# Step_counter.net
KiCad netlist of a schematic drawn in EAGLE
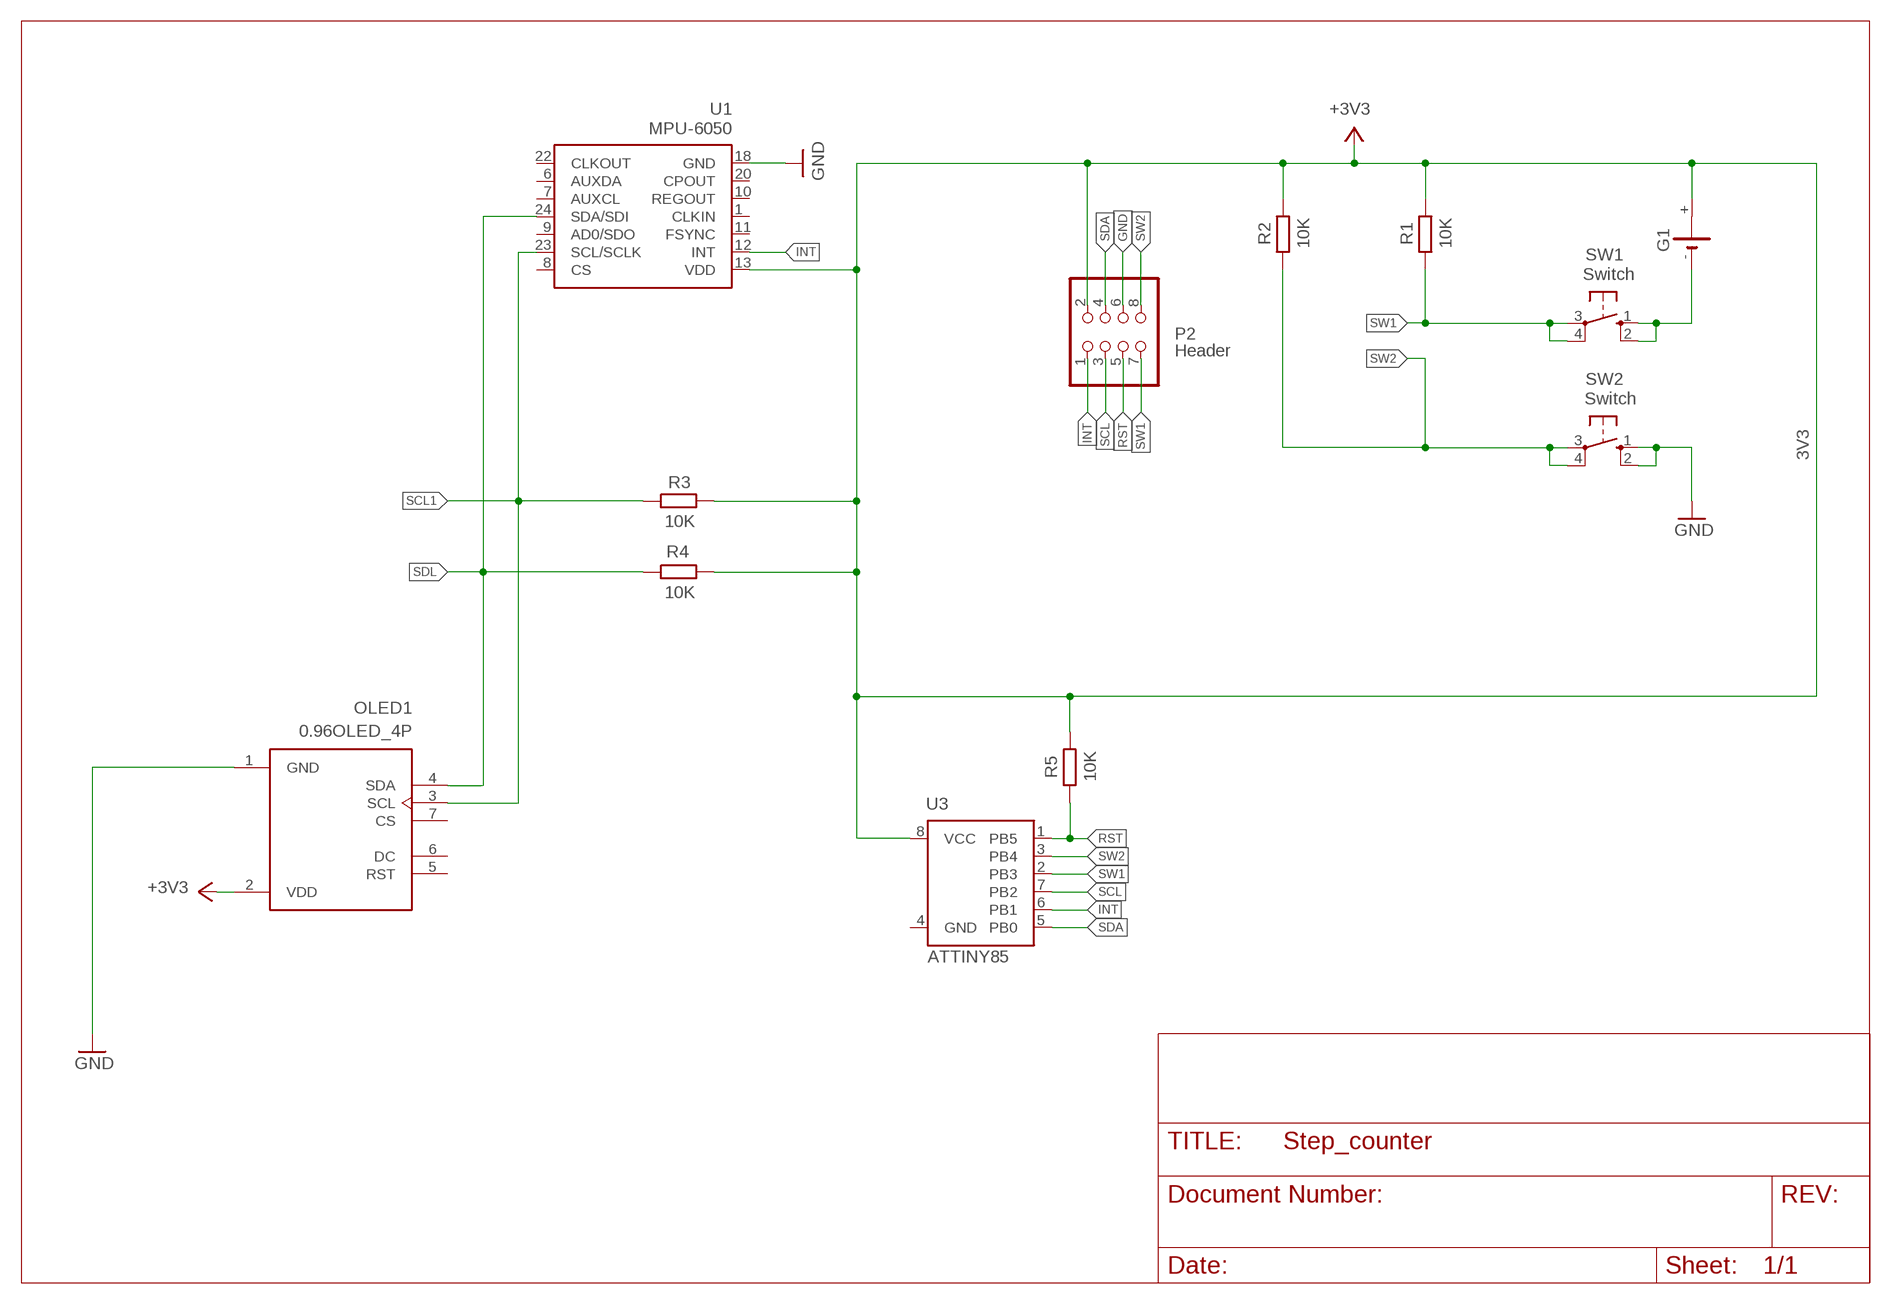
[diagram p0: schematic, sheet 1]

(export (version "E")
  (design (tool "Eeschema 10.0.6"))
  (components
    (comp (ref "G1")
      (value "3V3")
      (footprint "eagle-import:CR2032V")
      (libsource (lib "eagle-import") (part "CR2032V"))
    )
    (comp (ref "OLED1")
      (value "0.96OLED_4P")
      (footprint "eagle-import:LCD_AOM12864A0-1.54WW-ANO")
      (fields (field (name "MF") "Orient Display") (field (name "MP") "AOM12864A0-1.54WW-ANO"))
      (libsource (lib "eagle-import") (part "AOM12864A0-1.54WW-ANO"))
    )
    (comp (ref "P2")
      (value "Header")
      (footprint "eagle-import:2X04")
      (libsource (lib "eagle-import") (part "PINHD-2X4"))
    )
    (comp (ref "R1")
      (value "10K")
      (footprint "eagle-import:0204_7")
      (libsource (lib "eagle-import") (part "R-EU_0204/7"))
    )
    (comp (ref "R2")
      (value "10K")
      (footprint "eagle-import:0204_7")
      (libsource (lib "eagle-import") (part "R-EU_0204/7"))
    )
    (comp (ref "R3")
      (value "10K")
      (footprint "eagle-import:0204_7")
      (libsource (lib "eagle-import") (part "R-EU_0204/7"))
    )
    (comp (ref "R4")
      (value "10K")
      (footprint "eagle-import:0204_7")
      (libsource (lib "eagle-import") (part "R-EU_0204/7"))
    )
    (comp (ref "R5")
      (value "10K")
      (footprint "eagle-import:0204_7")
      (libsource (lib "eagle-import") (part "R-EU_0204/7"))
    )
    (comp (ref "SW1")
      (value "Switch")
      (footprint "eagle-import:B3F-10XX")
      (fields (field (name "MPN") "B3F-1000"))
      (libsource (lib "eagle-import") (part "10-XX"))
    )
    (comp (ref "SW2")
      (value "Switch")
      (footprint "eagle-import:B3F-10XX")
      (fields (field (name "MPN") "B3F-1000"))
      (libsource (lib "eagle-import") (part "10-XX"))
    )
    (comp (ref "U1")
      (value "MPU-6050")
      (footprint "eagle-import:QFN-24-EP")
      (libsource (lib "eagle-import") (part "MPU-6000"))
    )
    (comp (ref "U3")
      (value "ATTINY85")
      (footprint "eagle-import:ATTINY85")
      (libsource (lib "eagle-import") (part "ATTINY85"))
    )
  )
  (nets
    (net (code "1") (name "+3V3") (class "Default")
      (node (ref "G1") (pin "+") (pinfunction "+_+") (pintype "passive"))
      (node (ref "OLED1") (pin "2") (pinfunction "VDD_2") (pintype "power_in"))
      (node (ref "P2") (pin "2") (pinfunction "2_2") (pintype "passive"))
      (node (ref "R1") (pin "2") (pinfunction "2_2") (pintype "passive"))
      (node (ref "R2") (pin "2") (pinfunction "2_2") (pintype "passive"))
      (node (ref "R3") (pin "2") (pinfunction "2_2") (pintype "passive"))
      (node (ref "R4") (pin "2") (pinfunction "2_2") (pintype "passive"))
      (node (ref "R5") (pin "2") (pinfunction "2_2") (pintype "passive"))
      (node (ref "U1") (pin "13") (pinfunction "VDD_13") (pintype "bidirectional"))
      (node (ref "U3") (pin "8") (pinfunction "VCC_8") (pintype "bidirectional"))
    )
    (net (code "2") (name "GND") (class "Default")
      (node (ref "G1") (pin "-") (pinfunction "-_-") (pintype "passive"))
      (node (ref "OLED1") (pin "1") (pinfunction "GND_1") (pintype "power_in"))
      (node (ref "P2") (pin "6") (pinfunction "6_6") (pintype "passive"))
      (node (ref "SW1") (pin "1") (pinfunction "S_1") (pintype "passive"))
      (node (ref "SW1") (pin "2") (pinfunction "S1_2") (pintype "passive"))
      (node (ref "SW2") (pin "1") (pinfunction "S_1") (pintype "passive"))
      (node (ref "SW2") (pin "2") (pinfunction "S1_2") (pintype "passive"))
      (node (ref "U1") (pin "18") (pinfunction "GND_18") (pintype "bidirectional"))
    )
    (net (code "3") (name "INT") (class "Default")
      (node (ref "P2") (pin "1") (pinfunction "1_1") (pintype "passive"))
      (node (ref "U1") (pin "12") (pinfunction "INT_12") (pintype "bidirectional"))
      (node (ref "U3") (pin "6") (pinfunction "PB1_6") (pintype "bidirectional"))
    )
    (net (code "4") (name "RST") (class "Default")
      (node (ref "P2") (pin "5") (pinfunction "5_5") (pintype "passive"))
      (node (ref "R5") (pin "1") (pinfunction "1_1") (pintype "passive"))
      (node (ref "U3") (pin "1") (pinfunction "PB5_1") (pintype "bidirectional"))
    )
    (net (code "5") (name "SCL") (class "Default")
      (node (ref "P2") (pin "3") (pinfunction "3_3") (pintype "passive"))
      (node (ref "U3") (pin "7") (pinfunction "PB2_7") (pintype "bidirectional"))
    )
    (net (code "6") (name "SCL1") (class "Default")
      (node (ref "OLED1") (pin "3") (pinfunction "SCL_3") (pintype "input"))
      (node (ref "R3") (pin "1") (pinfunction "1_1") (pintype "passive"))
      (node (ref "U1") (pin "23") (pinfunction "SCL/SCLK_23") (pintype "bidirectional"))
    )
    (net (code "7") (name "SDA") (class "Default")
      (node (ref "P2") (pin "4") (pinfunction "4_4") (pintype "passive"))
      (node (ref "U3") (pin "5") (pinfunction "PB0_5") (pintype "bidirectional"))
    )
    (net (code "8") (name "SDL") (class "Default")
      (node (ref "OLED1") (pin "4") (pinfunction "SDA_4") (pintype "bidirectional"))
      (node (ref "R4") (pin "1") (pinfunction "1_1") (pintype "passive"))
      (node (ref "U1") (pin "24") (pinfunction "SDA/SDI_24") (pintype "bidirectional"))
    )
    (net (code "9") (name "SW1") (class "Default")
      (node (ref "P2") (pin "7") (pinfunction "7_7") (pintype "passive"))
      (node (ref "R1") (pin "1") (pinfunction "1_1") (pintype "passive"))
      (node (ref "SW1") (pin "3") (pinfunction "P_3") (pintype "passive"))
      (node (ref "SW1") (pin "4") (pinfunction "P1_4") (pintype "passive"))
      (node (ref "U3") (pin "2") (pinfunction "PB3_2") (pintype "bidirectional"))
    )
    (net (code "10") (name "SW2") (class "Default")
      (node (ref "P2") (pin "8") (pinfunction "8_8") (pintype "passive"))
      (node (ref "R2") (pin "1") (pinfunction "1_1") (pintype "passive"))
      (node (ref "SW2") (pin "3") (pinfunction "P_3") (pintype "passive"))
      (node (ref "SW2") (pin "4") (pinfunction "P1_4") (pintype "passive"))
      (node (ref "U3") (pin "3") (pinfunction "PB4_3") (pintype "bidirectional"))
    )
    (net (code "11") (name "unconnected-(G1-+-Pad+@1)") (class "Default")
      (node (ref "G1") (pin "+@1") (pinfunction "+_+@1") (pintype "passive"))
    )
    (net (code "12") (name "unconnected-(OLED1-CS-Pad7)") (class "Default")
      (node (ref "OLED1") (pin "7") (pinfunction "CS_7") (pintype "input"))
    )
    (net (code "13") (name "unconnected-(OLED1-DC-Pad6)") (class "Default")
      (node (ref "OLED1") (pin "6") (pinfunction "DC_6") (pintype "input"))
    )
    (net (code "14") (name "unconnected-(OLED1-RST-Pad5)") (class "Default")
      (node (ref "OLED1") (pin "5") (pinfunction "RST_5") (pintype "input"))
    )
    (net (code "15") (name "unconnected-(U1-AD0{slash}SDO-Pad9)") (class "Default")
      (node (ref "U1") (pin "9") (pinfunction "AD0/SDO_9") (pintype "bidirectional"))
    )
    (net (code "16") (name "unconnected-(U1-AUXCL-Pad7)") (class "Default")
      (node (ref "U1") (pin "7") (pinfunction "AUXCL_7") (pintype "bidirectional"))
    )
    (net (code "17") (name "unconnected-(U1-AUXDA-Pad6)") (class "Default")
      (node (ref "U1") (pin "6") (pinfunction "AUXDA_6") (pintype "bidirectional"))
    )
    (net (code "18") (name "unconnected-(U1-CLKIN-Pad1)") (class "Default")
      (node (ref "U1") (pin "1") (pinfunction "CLKIN_1") (pintype "bidirectional"))
    )
    (net (code "19") (name "unconnected-(U1-CLKOUT-Pad22)") (class "Default")
      (node (ref "U1") (pin "22") (pinfunction "CLKOUT_22") (pintype "bidirectional"))
    )
    (net (code "20") (name "unconnected-(U1-CPOUT-Pad20)") (class "Default")
      (node (ref "U1") (pin "20") (pinfunction "CPOUT_20") (pintype "bidirectional"))
    )
    (net (code "21") (name "unconnected-(U1-CS-Pad8)") (class "Default")
      (node (ref "U1") (pin "8") (pinfunction "CS_8") (pintype "bidirectional"))
    )
    (net (code "22") (name "unconnected-(U1-FSYNC-Pad11)") (class "Default")
      (node (ref "U1") (pin "11") (pinfunction "FSYNC_11") (pintype "bidirectional"))
    )
    (net (code "23") (name "unconnected-(U1-REGOUT-Pad10)") (class "Default")
      (node (ref "U1") (pin "10") (pinfunction "REGOUT_10") (pintype "bidirectional"))
    )
    (net (code "24") (name "unconnected-(U3-GND-Pad4)") (class "Default")
      (node (ref "U3") (pin "4") (pinfunction "GND_4") (pintype "bidirectional"))
    )
  )
)
